# usain_bot_chasis.net
KiCad netlist of a schematic drawn in EAGLE
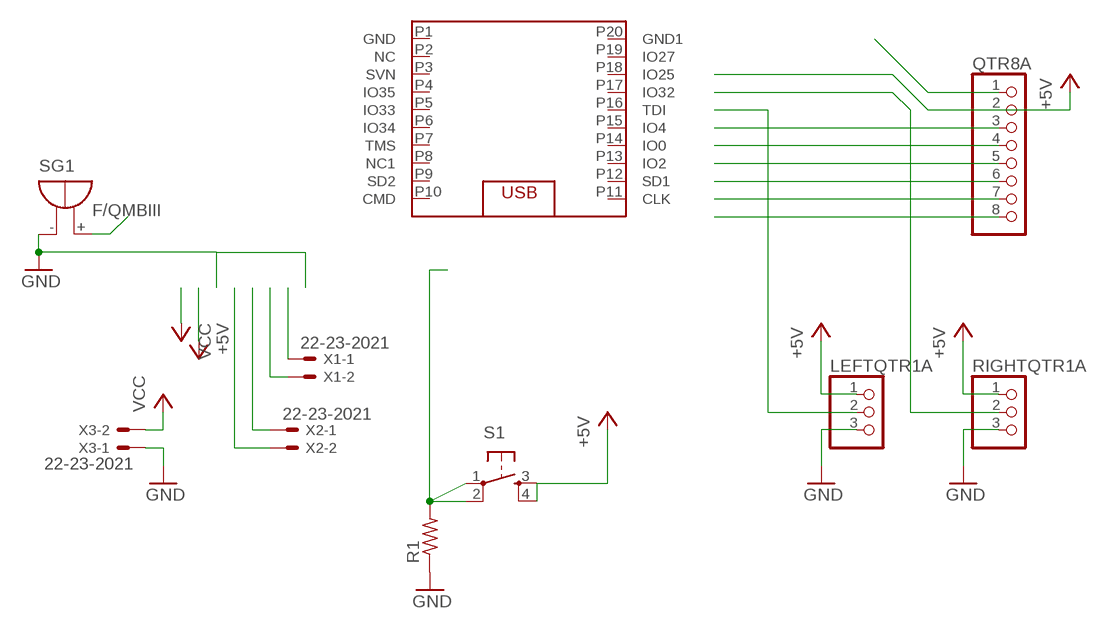
[diagram p0: schematic, sheet 1]

(export (version "E")
  (design (tool "Eeschema 10.0.6"))
  (components
    (comp (ref "LEFTQTR1A")
      (value "PINHD-1X3")
      (footprint "eagle-import:1X03")
      (libsource (lib "eagle-import") (part "PINHD-1X3"))
    )
    (comp (ref "QTR8A")
      (value "PINHD-1X8BIG")
      (footprint "eagle-import:1X08-BIG")
      (libsource (lib "eagle-import") (part "PINHD-1X8BIG"))
    )
    (comp (ref "R1")
      (value "R-US_0207/7")
      (footprint "eagle-import:0207_7")
      (libsource (lib "eagle-import") (part "R-US_0207/7"))
    )
    (comp (ref "RIGHTQTR1A")
      (value "PINHD-1X3")
      (footprint "eagle-import:1X03")
      (libsource (lib "eagle-import") (part "PINHD-1X3"))
    )
    (comp (ref "S1")
      (value "TAC_SWITCHPTH")
      (footprint "eagle-import:TACTILE-PTH")
      (libsource (lib "eagle-import") (part "TAC_SWITCHPTH"))
    )
    (comp (ref "SG1")
      (value "F/QMBIII")
      (footprint "eagle-import:F_QMBIII")
      (libsource (lib "eagle-import") (part "F/QMBIII"))
    )
    (comp (ref "U$1")
      (value "ESP32_MINI_KIT")
      (footprint "eagle-import:ESP32_MINI_KIT")
      (libsource (lib "eagle-import") (part "ESP32_MINI_KIT"))
    )
    (comp (ref "X1")
      (value "22-23-2021")
      (footprint "eagle-import:22-23-2021")
      (fields (field (name "MF") "MOLEX"))
      (libsource (lib "eagle-import") (part "22-23-2021"))
    )
    (comp (ref "X2")
      (value "22-23-2021")
      (footprint "eagle-import:22-23-2021")
      (fields (field (name "MF") "MOLEX"))
      (libsource (lib "eagle-import") (part "22-23-2021"))
    )
    (comp (ref "X3")
      (value "22-23-2021")
      (footprint "eagle-import:22-23-2021")
      (fields (field (name "MF") "MOLEX"))
      (libsource (lib "eagle-import") (part "22-23-2021"))
    )
  )
  (nets
    (net (code "1") (name "+5V") (class "Default")
      (node (ref "LEFTQTR1A") (pin "1") (pinfunction "1_1") (pintype "passive"))
      (node (ref "QTR8A") (pin "2") (pinfunction "2_2") (pintype "passive"))
      (node (ref "RIGHTQTR1A") (pin "1") (pinfunction "1_1") (pintype "passive"))
      (node (ref "S1") (pin "3") (pinfunction "3_3") (pintype "passive"))
      (node (ref "S1") (pin "4") (pinfunction "4_4") (pintype "passive"))
    )
    (net (code "2") (name "GND") (class "Default")
      (node (ref "LEFTQTR1A") (pin "3") (pinfunction "3_3") (pintype "passive"))
      (node (ref "R1") (pin "1") (pinfunction "1_1") (pintype "passive"))
      (node (ref "RIGHTQTR1A") (pin "3") (pinfunction "3_3") (pintype "passive"))
      (node (ref "SG1") (pin "-") (pinfunction "+_-") (pintype "passive"))
      (node (ref "X3") (pin "1") (pinfunction "S_1") (pintype "passive"))
    )
    (net (code "3") (name "Net-(R1-Pad2)") (class "Default")
      (node (ref "R1") (pin "2") (pinfunction "2_2") (pintype "passive"))
      (node (ref "S1") (pin "1") (pinfunction "1_1") (pintype "passive"))
      (node (ref "S1") (pin "2") (pinfunction "2_2") (pintype "passive"))
    )
    (net (code "4") (name "VCC") (class "Default")
      (node (ref "X3") (pin "2") (pinfunction "S_2") (pintype "passive"))
    )
    (net (code "5") (name "unconnected-(LEFTQTR1A-Pad2)") (class "Default")
      (node (ref "LEFTQTR1A") (pin "2") (pinfunction "2_2") (pintype "passive"))
    )
    (net (code "6") (name "unconnected-(QTR8A-Pad1)") (class "Default")
      (node (ref "QTR8A") (pin "1") (pinfunction "1_1") (pintype "passive"))
    )
    (net (code "7") (name "unconnected-(QTR8A-Pad3)") (class "Default")
      (node (ref "QTR8A") (pin "3") (pinfunction "3_3") (pintype "passive"))
    )
    (net (code "8") (name "unconnected-(QTR8A-Pad4)") (class "Default")
      (node (ref "QTR8A") (pin "4") (pinfunction "4_4") (pintype "passive"))
    )
    (net (code "9") (name "unconnected-(QTR8A-Pad5)") (class "Default")
      (node (ref "QTR8A") (pin "5") (pinfunction "5_5") (pintype "passive"))
    )
    (net (code "10") (name "unconnected-(QTR8A-Pad6)") (class "Default")
      (node (ref "QTR8A") (pin "6") (pinfunction "6_6") (pintype "passive"))
    )
    (net (code "11") (name "unconnected-(QTR8A-Pad7)") (class "Default")
      (node (ref "QTR8A") (pin "7") (pinfunction "7_7") (pintype "passive"))
    )
    (net (code "12") (name "unconnected-(QTR8A-Pad8)") (class "Default")
      (node (ref "QTR8A") (pin "8") (pinfunction "8_8") (pintype "passive"))
    )
    (net (code "13") (name "unconnected-(RIGHTQTR1A-Pad2)") (class "Default")
      (node (ref "RIGHTQTR1A") (pin "2") (pinfunction "2_2") (pintype "passive"))
    )
    (net (code "14") (name "unconnected-(SG1---Pad+)") (class "Default")
      (node (ref "SG1") (pin "+") (pinfunction "-_+") (pintype "passive"))
    )
    (net (code "15") (name "unconnected-(U$1-CLK-PadP11)") (class "Default")
      (node (ref "U$1") (pin "P11") (pinfunction "CLK_P11") (pintype "bidirectional"))
    )
    (net (code "16") (name "unconnected-(U$1-CMD-PadP10)") (class "Default")
      (node (ref "U$1") (pin "P10") (pinfunction "CMD_P10") (pintype "bidirectional"))
    )
    (net (code "17") (name "unconnected-(U$1-GND-PadP1)") (class "Default")
      (node (ref "U$1") (pin "P1") (pinfunction "GND_P1") (pintype "bidirectional"))
    )
    (net (code "18") (name "unconnected-(U$1-GND1-PadP20)") (class "Default")
      (node (ref "U$1") (pin "P20") (pinfunction "GND1_P20") (pintype "bidirectional"))
    )
    (net (code "19") (name "unconnected-(U$1-IO0-PadP14)") (class "Default")
      (node (ref "U$1") (pin "P14") (pinfunction "IO0_P14") (pintype "bidirectional"))
    )
    (net (code "20") (name "unconnected-(U$1-IO2-PadP13)") (class "Default")
      (node (ref "U$1") (pin "P13") (pinfunction "IO2_P13") (pintype "bidirectional"))
    )
    (net (code "21") (name "unconnected-(U$1-IO4-PadP15)") (class "Default")
      (node (ref "U$1") (pin "P15") (pinfunction "IO4_P15") (pintype "bidirectional"))
    )
    (net (code "22") (name "unconnected-(U$1-IO25-PadP18)") (class "Default")
      (node (ref "U$1") (pin "P18") (pinfunction "IO25_P18") (pintype "bidirectional"))
    )
    (net (code "23") (name "unconnected-(U$1-IO27-PadP19)") (class "Default")
      (node (ref "U$1") (pin "P19") (pinfunction "IO27_P19") (pintype "bidirectional"))
    )
    (net (code "24") (name "unconnected-(U$1-IO32-PadP17)") (class "Default")
      (node (ref "U$1") (pin "P17") (pinfunction "IO32_P17") (pintype "bidirectional"))
    )
    (net (code "25") (name "unconnected-(U$1-IO33-PadP5)") (class "Default")
      (node (ref "U$1") (pin "P5") (pinfunction "IO33_P5") (pintype "bidirectional"))
    )
    (net (code "26") (name "unconnected-(U$1-IO34-PadP6)") (class "Default")
      (node (ref "U$1") (pin "P6") (pinfunction "IO34_P6") (pintype "bidirectional"))
    )
    (net (code "27") (name "unconnected-(U$1-IO35-PadP4)") (class "Default")
      (node (ref "U$1") (pin "P4") (pinfunction "IO35_P4") (pintype "bidirectional"))
    )
    (net (code "28") (name "unconnected-(U$1-NC-PadP2)") (class "Default")
      (node (ref "U$1") (pin "P2") (pinfunction "NC_P2") (pintype "bidirectional"))
    )
    (net (code "29") (name "unconnected-(U$1-NC1-PadP8)") (class "Default")
      (node (ref "U$1") (pin "P8") (pinfunction "NC1_P8") (pintype "bidirectional"))
    )
    (net (code "30") (name "unconnected-(U$1-SD1-PadP12)") (class "Default")
      (node (ref "U$1") (pin "P12") (pinfunction "SD1_P12") (pintype "bidirectional"))
    )
    (net (code "31") (name "unconnected-(U$1-SD2-PadP9)") (class "Default")
      (node (ref "U$1") (pin "P9") (pinfunction "SD2_P9") (pintype "bidirectional"))
    )
    (net (code "32") (name "unconnected-(U$1-SVN-PadP3)") (class "Default")
      (node (ref "U$1") (pin "P3") (pinfunction "SVN_P3") (pintype "bidirectional"))
    )
    (net (code "33") (name "unconnected-(U$1-TDI-PadP16)") (class "Default")
      (node (ref "U$1") (pin "P16") (pinfunction "TDI_P16") (pintype "bidirectional"))
    )
    (net (code "34") (name "unconnected-(U$1-TMS-PadP7)") (class "Default")
      (node (ref "U$1") (pin "P7") (pinfunction "TMS_P7") (pintype "bidirectional"))
    )
    (net (code "35") (name "unconnected-(X1A-S-Pad1)") (class "Default")
      (node (ref "X1") (pin "1") (pinfunction "S_1") (pintype "passive"))
    )
    (net (code "36") (name "unconnected-(X1B-S-Pad2)") (class "Default")
      (node (ref "X1") (pin "2") (pinfunction "S_2") (pintype "passive"))
    )
    (net (code "37") (name "unconnected-(X2A-S-Pad1)") (class "Default")
      (node (ref "X2") (pin "1") (pinfunction "S_1") (pintype "passive"))
    )
    (net (code "38") (name "unconnected-(X2B-S-Pad2)") (class "Default")
      (node (ref "X2") (pin "2") (pinfunction "S_2") (pintype "passive"))
    )
  )
)
